# Sheet1.net
KiCad netlist of a schematic drawn in Altium Designer
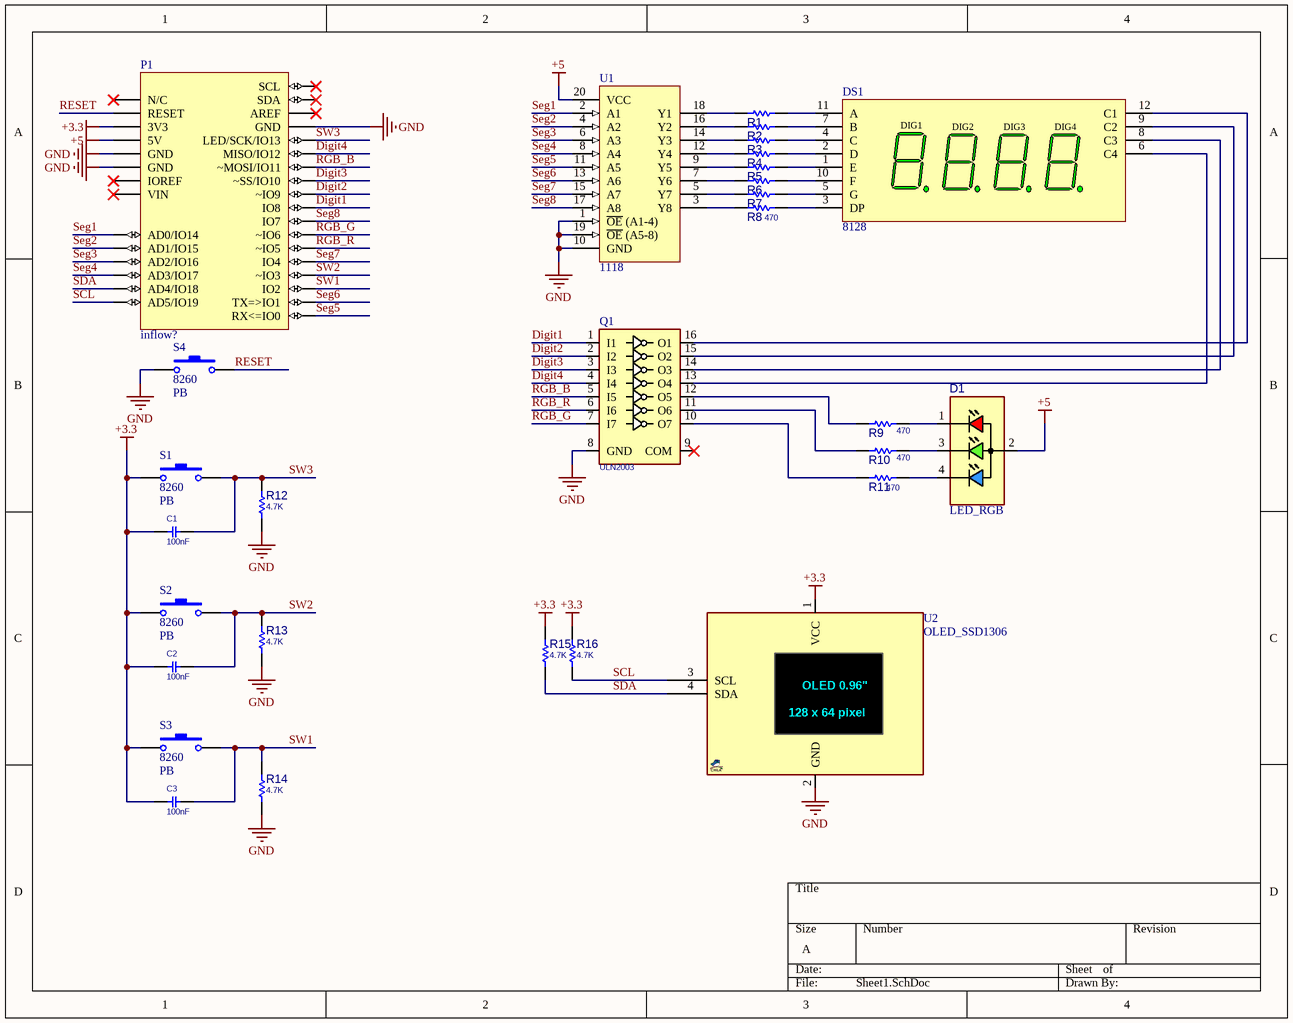
[diagram p0: Sheet1.SchDoc]

(export (version "E")
  (design (tool "Eeschema 10.0.6"))
  (components
    (comp (ref "C1")
      (value "100nF")
      (footprint "C_CER_D3")
      (description "CAP, THD, CER MULTI LAYER,")
      (fields (field (name "MANF_P#") "MANF_PART#") (field (name "MANF") "MANF"))
      (libsource (lib "Chila_PCB") (part "CAP_THD_CERML"))
    )
    (comp (ref "C2")
      (value "100nF")
      (footprint "C_CER_D3")
      (description "CAP, THD, CER MULTI LAYER,")
      (fields (field (name "MANF_P#") "MANF_PART#") (field (name "MANF") "MANF"))
      (libsource (lib "Chila_PCB") (part "CAP_THD_CERML"))
    )
    (comp (ref "C3")
      (value "100nF")
      (footprint "C_CER_D3")
      (description "CAP, THD, CER MULTI LAYER,")
      (fields (field (name "MANF_P#") "MANF_PART#") (field (name "MANF") "MANF"))
      (libsource (lib "Chila_PCB") (part "CAP_THD_CERML"))
    )
    (comp (ref "D1")
      (value "LED_RGB")
      (footprint "LED5RGB")
      (description "LED, THD, 5MM, RGB COMMON CATHODE")
      (fields (field (name "MANF_P#") "YSL-R596CR3G4B5C-C10") (field (name "MANF") "CHINA YOUNG"))
      (libsource (lib "Chila_PCB") (part "LED_THD_5MM_RGB_CA"))
    )
    (comp (ref "DS1")
      (value "4Digit, Red")
      (footprint "7Seg-MPX4-30.2x14.1mm")
      (description "7Segment-MPX4-CC")
      (fields (field (name "INFLOW") "8128"))
      (libsource (lib "aKaReZa") (part "ModSen_7Seg_MPX4_CC"))
    )
    (comp (ref "P1")
      (value "UNO")
      (footprint "Arduino_uno_S_3")
      (description "Arduino uno slave")
      (fields (field (name "INFLOW") "inflow?"))
      (libsource (lib "aKaReZa") (part "Con_Arduino_UNO_S"))
    )
    (comp (ref "Q1")
      (value "ULN2003")
      (footprint "DIP_16")
      (description "Darlington, 7-CH, 50V, 0.5A")
      (fields (field (name "MANF_P#") "ULN2003A") (field (name "MANF") "DIODES"))
      (libsource (lib "Chila_PCB") (part "ULN2003_DIP16"))
    )
    (comp (ref "R1")
      (value "470")
      (footprint "R1206")
      (description "RESISTOR, SMD")
      (libsource (lib "Chila_PCB") (part "RES_SMD_1206"))
    )
    (comp (ref "R2")
      (value "470")
      (footprint "R1206")
      (description "RESISTOR, SMD")
      (libsource (lib "Chila_PCB") (part "RES_SMD_1206"))
    )
    (comp (ref "R3")
      (value "470")
      (footprint "R1206")
      (description "RESISTOR, SMD")
      (libsource (lib "Chila_PCB") (part "RES_SMD_1206"))
    )
    (comp (ref "R4")
      (value "470")
      (footprint "R1206")
      (description "RESISTOR, SMD")
      (libsource (lib "Chila_PCB") (part "RES_SMD_1206"))
    )
    (comp (ref "R5")
      (value "470")
      (footprint "R1206")
      (description "RESISTOR, SMD")
      (libsource (lib "Chila_PCB") (part "RES_SMD_1206"))
    )
    (comp (ref "R6")
      (value "470")
      (footprint "R1206")
      (description "RESISTOR, SMD")
      (libsource (lib "Chila_PCB") (part "RES_SMD_1206"))
    )
    (comp (ref "R7")
      (value "470")
      (footprint "R1206")
      (description "RESISTOR, SMD")
      (libsource (lib "Chila_PCB") (part "RES_SMD_1206"))
    )
    (comp (ref "R8")
      (value "470")
      (footprint "R1206")
      (description "RESISTOR, SMD")
      (libsource (lib "Chila_PCB") (part "RES_SMD_1206"))
    )
    (comp (ref "R9")
      (value "470")
      (footprint "R1206")
      (description "RESISTOR, SMD")
      (libsource (lib "Chila_PCB") (part "RES_SMD_1206"))
    )
    (comp (ref "R10")
      (value "470")
      (footprint "R1206")
      (description "RESISTOR, SMD")
      (libsource (lib "Chila_PCB") (part "RES_SMD_1206"))
    )
    (comp (ref "R11")
      (value "470")
      (footprint "R1206")
      (description "RESISTOR, SMD")
      (libsource (lib "Chila_PCB") (part "RES_SMD_1206"))
    )
    (comp (ref "R12")
      (value "4.7K")
      (footprint "R1206")
      (description "RESISTOR, SMD")
      (libsource (lib "Chila_PCB") (part "RES_SMD_1206"))
    )
    (comp (ref "R13")
      (value "4.7K")
      (footprint "R1206")
      (description "RESISTOR, SMD")
      (libsource (lib "Chila_PCB") (part "RES_SMD_1206"))
    )
    (comp (ref "R14")
      (value "4.7K")
      (footprint "R1206")
      (description "RESISTOR, SMD")
      (libsource (lib "Chila_PCB") (part "RES_SMD_1206"))
    )
    (comp (ref "R15")
      (value "4.7K")
      (footprint "R1206")
      (description "RESISTOR, SMD")
      (libsource (lib "Chila_PCB") (part "RES_SMD_1206"))
    )
    (comp (ref "R16")
      (value "4.7K")
      (footprint "R1206")
      (description "RESISTOR, SMD")
      (libsource (lib "Chila_PCB") (part "RES_SMD_1206"))
    )
    (comp (ref "S1")
      (value "PB")
      (footprint "SW_PB_SMD_2PIN_SPST_6X3X2")
      (description "SMT Tactile ‎Switch")
      (fields (field (name "INFLOW") "8260"))
      (libsource (lib "aKaReZa") (part "SW_PushButton_2_SMD"))
    )
    (comp (ref "S2")
      (value "PB")
      (footprint "SW_PB_SMD_2PIN_SPST_6X3X2")
      (description "SMT Tactile ‎Switch")
      (fields (field (name "INFLOW") "8260"))
      (libsource (lib "aKaReZa") (part "SW_PushButton_2_SMD"))
    )
    (comp (ref "S3")
      (value "PB")
      (footprint "SW_PB_SMD_2PIN_SPST_6X3X2")
      (description "SMT Tactile ‎Switch")
      (fields (field (name "INFLOW") "8260"))
      (libsource (lib "aKaReZa") (part "SW_PushButton_2_SMD"))
    )
    (comp (ref "S4")
      (value "PB")
      (footprint "SW_PB_SMD_2PIN_SPST_6X3X2")
      (description "SMT Tactile ‎Switch")
      (fields (field (name "INFLOW") "8260"))
      (libsource (lib "aKaReZa") (part "SW_PushButton_2_SMD"))
    )
    (comp (ref "U1")
      (value "74HCT244")
      (footprint "PDIP20")
      (description "Octal Bus Buffer with 3 State Outputs (Non Inverted)")
      (fields (field (name "INFLOW") "1118"))
      (libsource (lib "aKaReZa") (part "IC_Logic_74HCT244"))
    )
    (comp (ref "U2")
      (value "OLED_SSD1306")
      (footprint "OLED_SSD1306_64_I2C")
      (description "OLED, SSD1306, 0.96\", 128X64, BREAKOUT I2C")
      (fields (field (name "MANF_P#") "OLED_SSD1306_I2C"))
      (libsource (lib "Chila_PCB") (part "OLED_SSD1306_64_I2C"))
    )
  )
  (nets
    (net (code "1") (name "+3.3") (class "Default")
      (node (ref "C1") (pin "1") (pinfunction "1_1") (pintype "passive"))
      (node (ref "C2") (pin "1") (pinfunction "1_1") (pintype "passive"))
      (node (ref "C3") (pin "1") (pinfunction "1_1") (pintype "passive"))
      (node (ref "P1") (pin "4") (pinfunction "3V3_4") (pintype "power_in"))
      (node (ref "R15") (pin "2") (pinfunction "2_2") (pintype "passive"))
      (node (ref "R16") (pin "2") (pinfunction "2_2") (pintype "passive"))
      (node (ref "S1") (pin "1") (pinfunction "1_1") (pintype "passive"))
      (node (ref "S2") (pin "1") (pinfunction "1_1") (pintype "passive"))
      (node (ref "S3") (pin "1") (pinfunction "1_1") (pintype "passive"))
      (node (ref "U2") (pin "1") (pinfunction "VCC_1") (pintype "passive"))
    )
    (net (code "2") (name "+5") (class "Default")
      (node (ref "D1") (pin "2") (pinfunction "C_2") (pintype "passive"))
      (node (ref "P1") (pin "5") (pinfunction "5V_5") (pintype "power_in"))
      (node (ref "U1") (pin "20") (pinfunction "VCC_20") (pintype "power_in"))
    )
    (net (code "3") (name "/Digit1") (class "Default")
      (node (ref "P1") (pin "23") (pinfunction "IO8_23") (pintype "bidirectional"))
      (node (ref "Q1") (pin "1") (pinfunction "I1_1") (pintype "passive"))
    )
    (net (code "4") (name "/Digit2") (class "Default")
      (node (ref "P1") (pin "24") (pinfunction "~IO9_24") (pintype "bidirectional"))
      (node (ref "Q1") (pin "2") (pinfunction "I2_2") (pintype "passive"))
    )
    (net (code "5") (name "/Digit3") (class "Default")
      (node (ref "P1") (pin "25") (pinfunction "~SS/IO10_25") (pintype "bidirectional"))
      (node (ref "Q1") (pin "3") (pinfunction "I3_3") (pintype "passive"))
    )
    (net (code "6") (name "/Digit4") (class "Default")
      (node (ref "P1") (pin "27") (pinfunction "MISO/IO12_27") (pintype "bidirectional"))
      (node (ref "Q1") (pin "4") (pinfunction "I4_4") (pintype "passive"))
    )
    (net (code "7") (name "/RESET") (class "Default")
      (node (ref "P1") (pin "3") (pinfunction "RESET_3") (pintype "passive"))
      (node (ref "S4") (pin "2") (pinfunction "2_2") (pintype "passive"))
    )
    (net (code "8") (name "/RGB_B") (class "Default")
      (node (ref "P1") (pin "26") (pinfunction "~MOSI/IO11_26") (pintype "bidirectional"))
      (node (ref "Q1") (pin "5") (pinfunction "I5_5") (pintype "passive"))
    )
    (net (code "9") (name "/RGB_G") (class "Default")
      (node (ref "P1") (pin "21") (pinfunction "~IO6_21") (pintype "bidirectional"))
      (node (ref "Q1") (pin "7") (pinfunction "I7_7") (pintype "passive"))
    )
    (net (code "10") (name "/RGB_R") (class "Default")
      (node (ref "P1") (pin "20") (pinfunction "~IO5_20") (pintype "bidirectional"))
      (node (ref "Q1") (pin "6") (pinfunction "I6_6") (pintype "passive"))
    )
    (net (code "11") (name "/SCL") (class "Default")
      (node (ref "P1") (pin "14") (pinfunction "AD5/IO19_14") (pintype "bidirectional"))
      (node (ref "R16") (pin "1") (pinfunction "1_1") (pintype "passive"))
      (node (ref "U2") (pin "3") (pinfunction "SCL_3") (pintype "passive"))
    )
    (net (code "12") (name "/SDA") (class "Default")
      (node (ref "P1") (pin "13") (pinfunction "AD4/IO18_13") (pintype "bidirectional"))
      (node (ref "R15") (pin "1") (pinfunction "1_1") (pintype "passive"))
      (node (ref "U2") (pin "4") (pinfunction "SDA_4") (pintype "passive"))
    )
    (net (code "13") (name "/SW1") (class "Default")
      (node (ref "C3") (pin "2") (pinfunction "2_2") (pintype "passive"))
      (node (ref "P1") (pin "17") (pinfunction "IO2_17") (pintype "bidirectional"))
      (node (ref "R14") (pin "2") (pinfunction "2_2") (pintype "passive"))
      (node (ref "S3") (pin "2") (pinfunction "2_2") (pintype "passive"))
    )
    (net (code "14") (name "/SW2") (class "Default")
      (node (ref "C2") (pin "2") (pinfunction "2_2") (pintype "passive"))
      (node (ref "P1") (pin "18") (pinfunction "~IO3_18") (pintype "bidirectional"))
      (node (ref "R13") (pin "2") (pinfunction "2_2") (pintype "passive"))
      (node (ref "S2") (pin "2") (pinfunction "2_2") (pintype "passive"))
    )
    (net (code "15") (name "/SW3") (class "Default")
      (node (ref "C1") (pin "2") (pinfunction "2_2") (pintype "passive"))
      (node (ref "P1") (pin "28") (pinfunction "LED/SCK/IO13_28") (pintype "bidirectional"))
      (node (ref "R12") (pin "2") (pinfunction "2_2") (pintype "passive"))
      (node (ref "S1") (pin "2") (pinfunction "2_2") (pintype "passive"))
    )
    (net (code "16") (name "/Seg1") (class "Default")
      (node (ref "P1") (pin "9") (pinfunction "AD0/IO14_9") (pintype "bidirectional"))
      (node (ref "U1") (pin "2") (pinfunction "A1_2") (pintype "input"))
    )
    (net (code "17") (name "/Seg2") (class "Default")
      (node (ref "P1") (pin "10") (pinfunction "AD1/IO15_10") (pintype "bidirectional"))
      (node (ref "U1") (pin "4") (pinfunction "A2_4") (pintype "input"))
    )
    (net (code "18") (name "/Seg3") (class "Default")
      (node (ref "P1") (pin "11") (pinfunction "AD2/IO16_11") (pintype "bidirectional"))
      (node (ref "U1") (pin "6") (pinfunction "A3_6") (pintype "input"))
    )
    (net (code "19") (name "/Seg4") (class "Default")
      (node (ref "P1") (pin "12") (pinfunction "AD3/IO17_12") (pintype "bidirectional"))
      (node (ref "U1") (pin "8") (pinfunction "A4_8") (pintype "input"))
    )
    (net (code "20") (name "/Seg5") (class "Default")
      (node (ref "P1") (pin "15") (pinfunction "RX<=IO0_15") (pintype "bidirectional"))
      (node (ref "U1") (pin "11") (pinfunction "A5_11") (pintype "input"))
    )
    (net (code "21") (name "/Seg6") (class "Default")
      (node (ref "P1") (pin "16") (pinfunction "TX=>IO1_16") (pintype "bidirectional"))
      (node (ref "U1") (pin "13") (pinfunction "A6_13") (pintype "input"))
    )
    (net (code "22") (name "/Seg7") (class "Default")
      (node (ref "P1") (pin "19") (pinfunction "IO4_19") (pintype "bidirectional"))
      (node (ref "U1") (pin "15") (pinfunction "A7_15") (pintype "input"))
    )
    (net (code "23") (name "/Seg8") (class "Default")
      (node (ref "P1") (pin "22") (pinfunction "IO7_22") (pintype "bidirectional"))
      (node (ref "U1") (pin "17") (pinfunction "A8_17") (pintype "input"))
    )
    (net (code "24") (name "GND") (class "Default")
      (node (ref "P1") (pin "29") (pinfunction "GND_29") (pintype "power_in"))
      (node (ref "P1") (pin "6") (pinfunction "GND_6") (pintype "power_in"))
      (node (ref "P1") (pin "7") (pinfunction "GND_7") (pintype "power_in"))
      (node (ref "Q1") (pin "8") (pinfunction "GND_8") (pintype "passive"))
      (node (ref "R12") (pin "1") (pinfunction "1_1") (pintype "passive"))
      (node (ref "R13") (pin "1") (pinfunction "1_1") (pintype "passive"))
      (node (ref "R14") (pin "1") (pinfunction "1_1") (pintype "passive"))
      (node (ref "S4") (pin "1") (pinfunction "1_1") (pintype "passive"))
      (node (ref "U1") (pin "1") (pinfunction "~{OE}_(A1-4)_1") (pintype "input"))
      (node (ref "U1") (pin "10") (pinfunction "GND_10") (pintype "power_in"))
      (node (ref "U1") (pin "19") (pinfunction "~{OE}_(A5-8)_19") (pintype "input"))
      (node (ref "U2") (pin "2") (pinfunction "GND_2") (pintype "passive"))
    )
    (net (code "25") (name "Net-(D1-BLU)") (class "Default")
      (node (ref "D1") (pin "4") (pinfunction "BLU_4") (pintype "passive"))
      (node (ref "R11") (pin "2") (pinfunction "2_2") (pintype "passive"))
    )
    (net (code "26") (name "Net-(D1-GRN)") (class "Default")
      (node (ref "D1") (pin "3") (pinfunction "GRN_3") (pintype "passive"))
      (node (ref "R10") (pin "2") (pinfunction "2_2") (pintype "passive"))
    )
    (net (code "27") (name "Net-(D1-RED)") (class "Default")
      (node (ref "D1") (pin "1") (pinfunction "RED_1") (pintype "passive"))
      (node (ref "R9") (pin "2") (pinfunction "2_2") (pintype "passive"))
    )
    (net (code "28") (name "Net-(DS1-A)") (class "Default")
      (node (ref "DS1") (pin "11") (pinfunction "A_11") (pintype "passive"))
      (node (ref "R1") (pin "2") (pinfunction "2_2") (pintype "passive"))
    )
    (net (code "29") (name "Net-(DS1-B)") (class "Default")
      (node (ref "DS1") (pin "7") (pinfunction "B_7") (pintype "passive"))
      (node (ref "R2") (pin "2") (pinfunction "2_2") (pintype "passive"))
    )
    (net (code "30") (name "Net-(DS1-C)") (class "Default")
      (node (ref "DS1") (pin "4") (pinfunction "C_4") (pintype "passive"))
      (node (ref "R3") (pin "2") (pinfunction "2_2") (pintype "passive"))
    )
    (net (code "31") (name "Net-(DS1-C1)") (class "Default")
      (node (ref "DS1") (pin "12") (pinfunction "C1_12") (pintype "passive"))
      (node (ref "Q1") (pin "16") (pinfunction "O1_16") (pintype "passive"))
    )
    (net (code "32") (name "Net-(DS1-C2)") (class "Default")
      (node (ref "DS1") (pin "9") (pinfunction "C2_9") (pintype "passive"))
      (node (ref "Q1") (pin "15") (pinfunction "O2_15") (pintype "passive"))
    )
    (net (code "33") (name "Net-(DS1-C3)") (class "Default")
      (node (ref "DS1") (pin "8") (pinfunction "C3_8") (pintype "passive"))
      (node (ref "Q1") (pin "14") (pinfunction "O3_14") (pintype "passive"))
    )
    (net (code "34") (name "Net-(DS1-C4)") (class "Default")
      (node (ref "DS1") (pin "6") (pinfunction "C4_6") (pintype "passive"))
      (node (ref "Q1") (pin "13") (pinfunction "O4_13") (pintype "passive"))
    )
    (net (code "35") (name "Net-(DS1-D)") (class "Default")
      (node (ref "DS1") (pin "2") (pinfunction "D_2") (pintype "passive"))
      (node (ref "R4") (pin "2") (pinfunction "2_2") (pintype "passive"))
    )
    (net (code "36") (name "Net-(DS1-DP)") (class "Default")
      (node (ref "DS1") (pin "3") (pinfunction "DP_3") (pintype "passive"))
      (node (ref "R8") (pin "2") (pinfunction "2_2") (pintype "passive"))
    )
    (net (code "37") (name "Net-(DS1-E)") (class "Default")
      (node (ref "DS1") (pin "1") (pinfunction "E_1") (pintype "passive"))
      (node (ref "R5") (pin "2") (pinfunction "2_2") (pintype "passive"))
    )
    (net (code "38") (name "Net-(DS1-F)") (class "Default")
      (node (ref "DS1") (pin "10") (pinfunction "F_10") (pintype "passive"))
      (node (ref "R6") (pin "2") (pinfunction "2_2") (pintype "passive"))
    )
    (net (code "39") (name "Net-(DS1-G)") (class "Default")
      (node (ref "DS1") (pin "5") (pinfunction "G_5") (pintype "passive"))
      (node (ref "R7") (pin "2") (pinfunction "2_2") (pintype "passive"))
    )
    (net (code "40") (name "Net-(Q1-O5)") (class "Default")
      (node (ref "Q1") (pin "12") (pinfunction "O5_12") (pintype "passive"))
      (node (ref "R9") (pin "1") (pinfunction "1_1") (pintype "passive"))
    )
    (net (code "41") (name "Net-(Q1-O6)") (class "Default")
      (node (ref "Q1") (pin "11") (pinfunction "O6_11") (pintype "passive"))
      (node (ref "R10") (pin "1") (pinfunction "1_1") (pintype "passive"))
    )
    (net (code "42") (name "Net-(Q1-O7)") (class "Default")
      (node (ref "Q1") (pin "10") (pinfunction "O7_10") (pintype "passive"))
      (node (ref "R11") (pin "1") (pinfunction "1_1") (pintype "passive"))
    )
    (net (code "43") (name "Net-(U1-Y1)") (class "Default")
      (node (ref "R1") (pin "1") (pinfunction "1_1") (pintype "passive"))
      (node (ref "U1") (pin "18") (pinfunction "Y1_18") (pintype "tri_state"))
    )
    (net (code "44") (name "Net-(U1-Y2)") (class "Default")
      (node (ref "R2") (pin "1") (pinfunction "1_1") (pintype "passive"))
      (node (ref "U1") (pin "16") (pinfunction "Y2_16") (pintype "tri_state"))
    )
    (net (code "45") (name "Net-(U1-Y3)") (class "Default")
      (node (ref "R3") (pin "1") (pinfunction "1_1") (pintype "passive"))
      (node (ref "U1") (pin "14") (pinfunction "Y3_14") (pintype "tri_state"))
    )
    (net (code "46") (name "Net-(U1-Y4)") (class "Default")
      (node (ref "R4") (pin "1") (pinfunction "1_1") (pintype "passive"))
      (node (ref "U1") (pin "12") (pinfunction "Y4_12") (pintype "tri_state"))
    )
    (net (code "47") (name "Net-(U1-Y5)") (class "Default")
      (node (ref "R5") (pin "1") (pinfunction "1_1") (pintype "passive"))
      (node (ref "U1") (pin "9") (pinfunction "Y5_9") (pintype "tri_state"))
    )
    (net (code "48") (name "Net-(U1-Y6)") (class "Default")
      (node (ref "R6") (pin "1") (pinfunction "1_1") (pintype "passive"))
      (node (ref "U1") (pin "7") (pinfunction "Y6_7") (pintype "tri_state"))
    )
    (net (code "49") (name "Net-(U1-Y7)") (class "Default")
      (node (ref "R7") (pin "1") (pinfunction "1_1") (pintype "passive"))
      (node (ref "U1") (pin "5") (pinfunction "Y7_5") (pintype "tri_state"))
    )
    (net (code "50") (name "Net-(U1-Y8)") (class "Default")
      (node (ref "R8") (pin "1") (pinfunction "1_1") (pintype "passive"))
      (node (ref "U1") (pin "3") (pinfunction "Y8_3") (pintype "tri_state"))
    )
    (net (code "51") (name "unconnected-(P1-AREF-Pad30)") (class "Default")
      (node (ref "P1") (pin "30") (pinfunction "AREF_30") (pintype "passive+no_connect"))
    )
    (net (code "52") (name "unconnected-(P1-IOREF-Pad2)") (class "Default")
      (node (ref "P1") (pin "2") (pinfunction "IOREF_2") (pintype "power_in+no_connect"))
    )
    (net (code "53") (name "unconnected-(P1-N{slash}C-Pad1)") (class "Default")
      (node (ref "P1") (pin "1") (pinfunction "N/C_1") (pintype "passive+no_connect"))
    )
    (net (code "54") (name "unconnected-(P1-SCL-Pad32)") (class "Default")
      (node (ref "P1") (pin "32") (pinfunction "SCL_32") (pintype "bidirectional+no_connect"))
    )
    (net (code "55") (name "unconnected-(P1-SDA-Pad31)") (class "Default")
      (node (ref "P1") (pin "31") (pinfunction "SDA_31") (pintype "bidirectional+no_connect"))
    )
    (net (code "56") (name "unconnected-(P1-VIN-Pad8)") (class "Default")
      (node (ref "P1") (pin "8") (pinfunction "VIN_8") (pintype "power_in+no_connect"))
    )
    (net (code "57") (name "unconnected-(Q1-COM-Pad9)") (class "Default")
      (node (ref "Q1") (pin "9") (pinfunction "COM_9") (pintype "passive+no_connect"))
    )
  )
)
